# Aux_Board.net
KiCad netlist of a schematic drawn in EAGLE
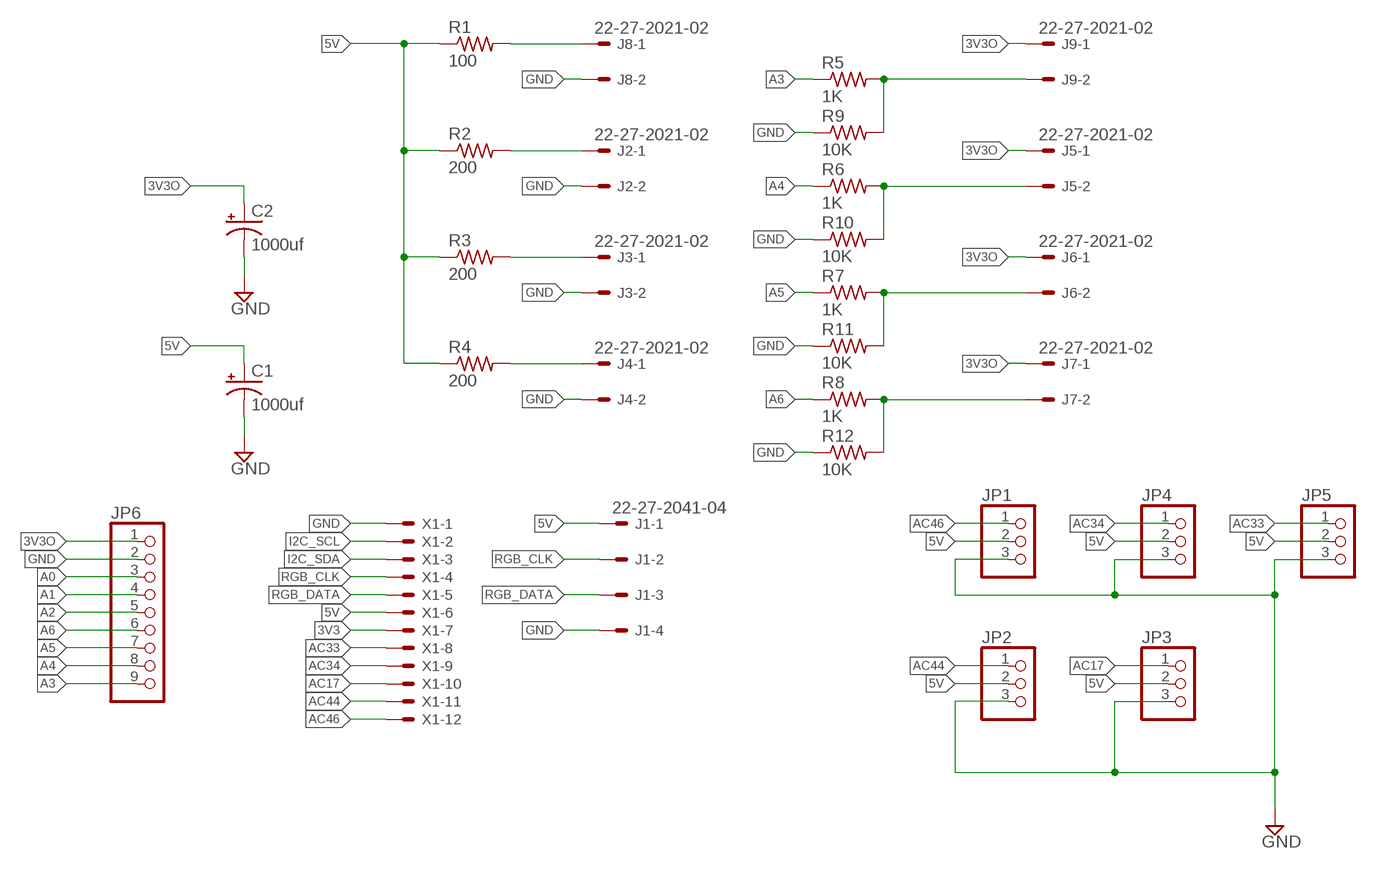
[diagram p0: schematic, sheet 1]

(export (version "E")
  (design (tool "Eeschema 10.0.6"))
  (components
    (comp (ref "C1")
      (value "1000uf")
      (footprint "eagle-import:E5-8,5")
      (libsource (lib "eagle-import") (part "CPOL-USE5-8.5"))
    )
    (comp (ref "C2")
      (value "1000uf")
      (footprint "eagle-import:E5-8,5")
      (libsource (lib "eagle-import") (part "CPOL-USE5-8.5"))
    )
    (comp (ref "J1")
      (value "22-27-2041-04")
      (footprint "eagle-import:6410-04")
      (libsource (lib "eagle-import") (part "22-?-0427-2041"))
    )
    (comp (ref "J2")
      (value "22-27-2021-02")
      (footprint "eagle-import:6410-02")
      (libsource (lib "eagle-import") (part "22-?-0227-2021"))
    )
    (comp (ref "J3")
      (value "22-27-2021-02")
      (footprint "eagle-import:6410-02")
      (libsource (lib "eagle-import") (part "22-?-0227-2021"))
    )
    (comp (ref "J4")
      (value "22-27-2021-02")
      (footprint "eagle-import:6410-02")
      (libsource (lib "eagle-import") (part "22-?-0227-2021"))
    )
    (comp (ref "J5")
      (value "22-27-2021-02")
      (footprint "eagle-import:6410-02")
      (libsource (lib "eagle-import") (part "22-?-0227-2021"))
    )
    (comp (ref "J6")
      (value "22-27-2021-02")
      (footprint "eagle-import:6410-02")
      (libsource (lib "eagle-import") (part "22-?-0227-2021"))
    )
    (comp (ref "J7")
      (value "22-27-2021-02")
      (footprint "eagle-import:6410-02")
      (libsource (lib "eagle-import") (part "22-?-0227-2021"))
    )
    (comp (ref "J8")
      (value "22-27-2021-02")
      (footprint "eagle-import:6410-02")
      (libsource (lib "eagle-import") (part "22-?-0227-2021"))
    )
    (comp (ref "J9")
      (value "22-27-2021-02")
      (footprint "eagle-import:6410-02")
      (libsource (lib "eagle-import") (part "22-?-0227-2021"))
    )
    (comp (ref "JP1")
      (value "PINHD-1X3")
      (footprint "eagle-import:1X03")
      (libsource (lib "eagle-import") (part "PINHD-1X3"))
    )
    (comp (ref "JP2")
      (value "PINHD-1X3")
      (footprint "eagle-import:1X03")
      (libsource (lib "eagle-import") (part "PINHD-1X3"))
    )
    (comp (ref "JP3")
      (value "PINHD-1X3")
      (footprint "eagle-import:1X03")
      (libsource (lib "eagle-import") (part "PINHD-1X3"))
    )
    (comp (ref "JP4")
      (value "PINHD-1X3")
      (footprint "eagle-import:1X03")
      (libsource (lib "eagle-import") (part "PINHD-1X3"))
    )
    (comp (ref "JP5")
      (value "PINHD-1X3")
      (footprint "eagle-import:1X03")
      (libsource (lib "eagle-import") (part "PINHD-1X3"))
    )
    (comp (ref "JP6")
      (value "PINHD-1X9")
      (footprint "eagle-import:1X09-BIG")
      (libsource (lib "eagle-import") (part "PINHD-1X9"))
    )
    (comp (ref "R1")
      (value "100")
      (footprint "eagle-import:0207_10")
      (libsource (lib "eagle-import") (part "R-US_0207/10"))
    )
    (comp (ref "R2")
      (value "200")
      (footprint "eagle-import:0207_10")
      (libsource (lib "eagle-import") (part "R-US_0207/10"))
    )
    (comp (ref "R3")
      (value "200")
      (footprint "eagle-import:0207_10")
      (libsource (lib "eagle-import") (part "R-US_0207/10"))
    )
    (comp (ref "R4")
      (value "200")
      (footprint "eagle-import:0207_10")
      (libsource (lib "eagle-import") (part "R-US_0207/10"))
    )
    (comp (ref "R5")
      (value "1K")
      (footprint "eagle-import:0207_10")
      (libsource (lib "eagle-import") (part "R-US_0207/10"))
    )
    (comp (ref "R6")
      (value "1K")
      (footprint "eagle-import:0207_10")
      (libsource (lib "eagle-import") (part "R-US_0207/10"))
    )
    (comp (ref "R7")
      (value "1K")
      (footprint "eagle-import:0207_10")
      (libsource (lib "eagle-import") (part "R-US_0207/10"))
    )
    (comp (ref "R8")
      (value "1K")
      (footprint "eagle-import:0207_10")
      (libsource (lib "eagle-import") (part "R-US_0207/10"))
    )
    (comp (ref "R9")
      (value "10K")
      (footprint "eagle-import:0207_10")
      (libsource (lib "eagle-import") (part "R-US_0207/10"))
    )
    (comp (ref "R10")
      (value "10K")
      (footprint "eagle-import:0207_10")
      (libsource (lib "eagle-import") (part "R-US_0207/10"))
    )
    (comp (ref "R11")
      (value "10K")
      (footprint "eagle-import:0207_10")
      (libsource (lib "eagle-import") (part "R-US_0207/10"))
    )
    (comp (ref "R12")
      (value "10K")
      (footprint "eagle-import:0207_10")
      (libsource (lib "eagle-import") (part "R-US_0207/10"))
    )
    (comp (ref "X1")
      (value "KK-156-12")
      (footprint "eagle-import:KK-156-12")
      (libsource (lib "eagle-import") (part "KK-156-12"))
    )
  )
  (nets
    (net (code "1") (name "3V3") (class "Default")
      (node (ref "X1") (pin "7") (pinfunction "S_7") (pintype "passive"))
    )
    (net (code "2") (name "3V3O") (class "Default")
      (node (ref "C2") (pin "+") (pinfunction "+_+") (pintype "passive"))
      (node (ref "J5") (pin "1") (pinfunction "S_1") (pintype "passive"))
      (node (ref "J6") (pin "1") (pinfunction "S_1") (pintype "passive"))
      (node (ref "J7") (pin "1") (pinfunction "S_1") (pintype "passive"))
      (node (ref "J9") (pin "1") (pinfunction "S_1") (pintype "passive"))
      (node (ref "JP6") (pin "1") (pinfunction "1_1") (pintype "passive"))
    )
    (net (code "3") (name "5V") (class "Default")
      (node (ref "C1") (pin "+") (pinfunction "+_+") (pintype "passive"))
      (node (ref "J1") (pin "1") (pinfunction "S_1") (pintype "passive"))
      (node (ref "JP1") (pin "2") (pinfunction "2_2") (pintype "passive"))
      (node (ref "JP2") (pin "2") (pinfunction "2_2") (pintype "passive"))
      (node (ref "JP3") (pin "2") (pinfunction "2_2") (pintype "passive"))
      (node (ref "JP4") (pin "2") (pinfunction "2_2") (pintype "passive"))
      (node (ref "JP5") (pin "2") (pinfunction "2_2") (pintype "passive"))
      (node (ref "R1") (pin "1") (pinfunction "1_1") (pintype "passive"))
      (node (ref "R2") (pin "1") (pinfunction "1_1") (pintype "passive"))
      (node (ref "R3") (pin "1") (pinfunction "1_1") (pintype "passive"))
      (node (ref "R4") (pin "1") (pinfunction "1_1") (pintype "passive"))
      (node (ref "X1") (pin "6") (pinfunction "S_6") (pintype "passive"))
    )
    (net (code "4") (name "A0") (class "Default")
      (node (ref "JP6") (pin "3") (pinfunction "3_3") (pintype "passive"))
    )
    (net (code "5") (name "A1") (class "Default")
      (node (ref "JP6") (pin "4") (pinfunction "4_4") (pintype "passive"))
    )
    (net (code "6") (name "A2") (class "Default")
      (node (ref "JP6") (pin "5") (pinfunction "5_5") (pintype "passive"))
    )
    (net (code "7") (name "A3") (class "Default")
      (node (ref "JP6") (pin "9") (pinfunction "9_9") (pintype "passive"))
      (node (ref "R5") (pin "1") (pinfunction "1_1") (pintype "passive"))
    )
    (net (code "8") (name "A4") (class "Default")
      (node (ref "JP6") (pin "8") (pinfunction "8_8") (pintype "passive"))
      (node (ref "R6") (pin "1") (pinfunction "1_1") (pintype "passive"))
    )
    (net (code "9") (name "A5") (class "Default")
      (node (ref "JP6") (pin "7") (pinfunction "7_7") (pintype "passive"))
      (node (ref "R7") (pin "1") (pinfunction "1_1") (pintype "passive"))
    )
    (net (code "10") (name "A6") (class "Default")
      (node (ref "JP6") (pin "6") (pinfunction "6_6") (pintype "passive"))
      (node (ref "R8") (pin "1") (pinfunction "1_1") (pintype "passive"))
    )
    (net (code "11") (name "AC17") (class "Default")
      (node (ref "JP3") (pin "1") (pinfunction "1_1") (pintype "passive"))
      (node (ref "X1") (pin "10") (pinfunction "S_10") (pintype "passive"))
    )
    (net (code "12") (name "AC33") (class "Default")
      (node (ref "JP5") (pin "1") (pinfunction "1_1") (pintype "passive"))
      (node (ref "X1") (pin "8") (pinfunction "S_8") (pintype "passive"))
    )
    (net (code "13") (name "AC34") (class "Default")
      (node (ref "JP4") (pin "1") (pinfunction "1_1") (pintype "passive"))
      (node (ref "X1") (pin "9") (pinfunction "S_9") (pintype "passive"))
    )
    (net (code "14") (name "AC44") (class "Default")
      (node (ref "JP2") (pin "1") (pinfunction "1_1") (pintype "passive"))
      (node (ref "X1") (pin "11") (pinfunction "S_11") (pintype "passive"))
    )
    (net (code "15") (name "AC46") (class "Default")
      (node (ref "JP1") (pin "1") (pinfunction "1_1") (pintype "passive"))
      (node (ref "X1") (pin "12") (pinfunction "S_12") (pintype "passive"))
    )
    (net (code "16") (name "GND") (class "Default")
      (node (ref "C1") (pin "-") (pinfunction "-_-") (pintype "passive"))
      (node (ref "C2") (pin "-") (pinfunction "-_-") (pintype "passive"))
      (node (ref "J1") (pin "4") (pinfunction "S_4") (pintype "passive"))
      (node (ref "J2") (pin "2") (pinfunction "S_2") (pintype "passive"))
      (node (ref "J3") (pin "2") (pinfunction "S_2") (pintype "passive"))
      (node (ref "J4") (pin "2") (pinfunction "S_2") (pintype "passive"))
      (node (ref "J8") (pin "2") (pinfunction "S_2") (pintype "passive"))
      (node (ref "JP1") (pin "3") (pinfunction "3_3") (pintype "passive"))
      (node (ref "JP2") (pin "3") (pinfunction "3_3") (pintype "passive"))
      (node (ref "JP3") (pin "3") (pinfunction "3_3") (pintype "passive"))
      (node (ref "JP4") (pin "3") (pinfunction "3_3") (pintype "passive"))
      (node (ref "JP5") (pin "3") (pinfunction "3_3") (pintype "passive"))
      (node (ref "JP6") (pin "2") (pinfunction "2_2") (pintype "passive"))
      (node (ref "R10") (pin "1") (pinfunction "1_1") (pintype "passive"))
      (node (ref "R11") (pin "1") (pinfunction "1_1") (pintype "passive"))
      (node (ref "R12") (pin "1") (pinfunction "1_1") (pintype "passive"))
      (node (ref "R9") (pin "1") (pinfunction "1_1") (pintype "passive"))
      (node (ref "X1") (pin "1") (pinfunction "S_1") (pintype "passive"))
    )
    (net (code "17") (name "I2C_SCL") (class "Default")
      (node (ref "X1") (pin "2") (pinfunction "S_2") (pintype "passive"))
    )
    (net (code "18") (name "I2C_SDA") (class "Default")
      (node (ref "X1") (pin "3") (pinfunction "S_3") (pintype "passive"))
    )
    (net (code "19") (name "Net-(J2A-S)") (class "Default")
      (node (ref "J2") (pin "1") (pinfunction "S_1") (pintype "passive"))
      (node (ref "R2") (pin "2") (pinfunction "2_2") (pintype "passive"))
    )
    (net (code "20") (name "Net-(J3A-S)") (class "Default")
      (node (ref "J3") (pin "1") (pinfunction "S_1") (pintype "passive"))
      (node (ref "R3") (pin "2") (pinfunction "2_2") (pintype "passive"))
    )
    (net (code "21") (name "Net-(J4A-S)") (class "Default")
      (node (ref "J4") (pin "1") (pinfunction "S_1") (pintype "passive"))
      (node (ref "R4") (pin "2") (pinfunction "2_2") (pintype "passive"))
    )
    (net (code "22") (name "Net-(J5B-S)") (class "Default")
      (node (ref "J5") (pin "2") (pinfunction "S_2") (pintype "passive"))
      (node (ref "R10") (pin "2") (pinfunction "2_2") (pintype "passive"))
      (node (ref "R6") (pin "2") (pinfunction "2_2") (pintype "passive"))
    )
    (net (code "23") (name "Net-(J6B-S)") (class "Default")
      (node (ref "J6") (pin "2") (pinfunction "S_2") (pintype "passive"))
      (node (ref "R11") (pin "2") (pinfunction "2_2") (pintype "passive"))
      (node (ref "R7") (pin "2") (pinfunction "2_2") (pintype "passive"))
    )
    (net (code "24") (name "Net-(J7B-S)") (class "Default")
      (node (ref "J7") (pin "2") (pinfunction "S_2") (pintype "passive"))
      (node (ref "R12") (pin "2") (pinfunction "2_2") (pintype "passive"))
      (node (ref "R8") (pin "2") (pinfunction "2_2") (pintype "passive"))
    )
    (net (code "25") (name "Net-(J8A-S)") (class "Default")
      (node (ref "J8") (pin "1") (pinfunction "S_1") (pintype "passive"))
      (node (ref "R1") (pin "2") (pinfunction "2_2") (pintype "passive"))
    )
    (net (code "26") (name "Net-(J9B-S)") (class "Default")
      (node (ref "J9") (pin "2") (pinfunction "S_2") (pintype "passive"))
      (node (ref "R5") (pin "2") (pinfunction "2_2") (pintype "passive"))
      (node (ref "R9") (pin "2") (pinfunction "2_2") (pintype "passive"))
    )
    (net (code "27") (name "RGB_CLK") (class "Default")
      (node (ref "J1") (pin "2") (pinfunction "S_2") (pintype "passive"))
      (node (ref "X1") (pin "4") (pinfunction "S_4") (pintype "passive"))
    )
    (net (code "28") (name "RGB_DATA") (class "Default")
      (node (ref "J1") (pin "3") (pinfunction "S_3") (pintype "passive"))
      (node (ref "X1") (pin "5") (pinfunction "S_5") (pintype "passive"))
    )
  )
)
